# stm32f3driver3.net
KiCad netlist of a schematic drawn in EAGLE
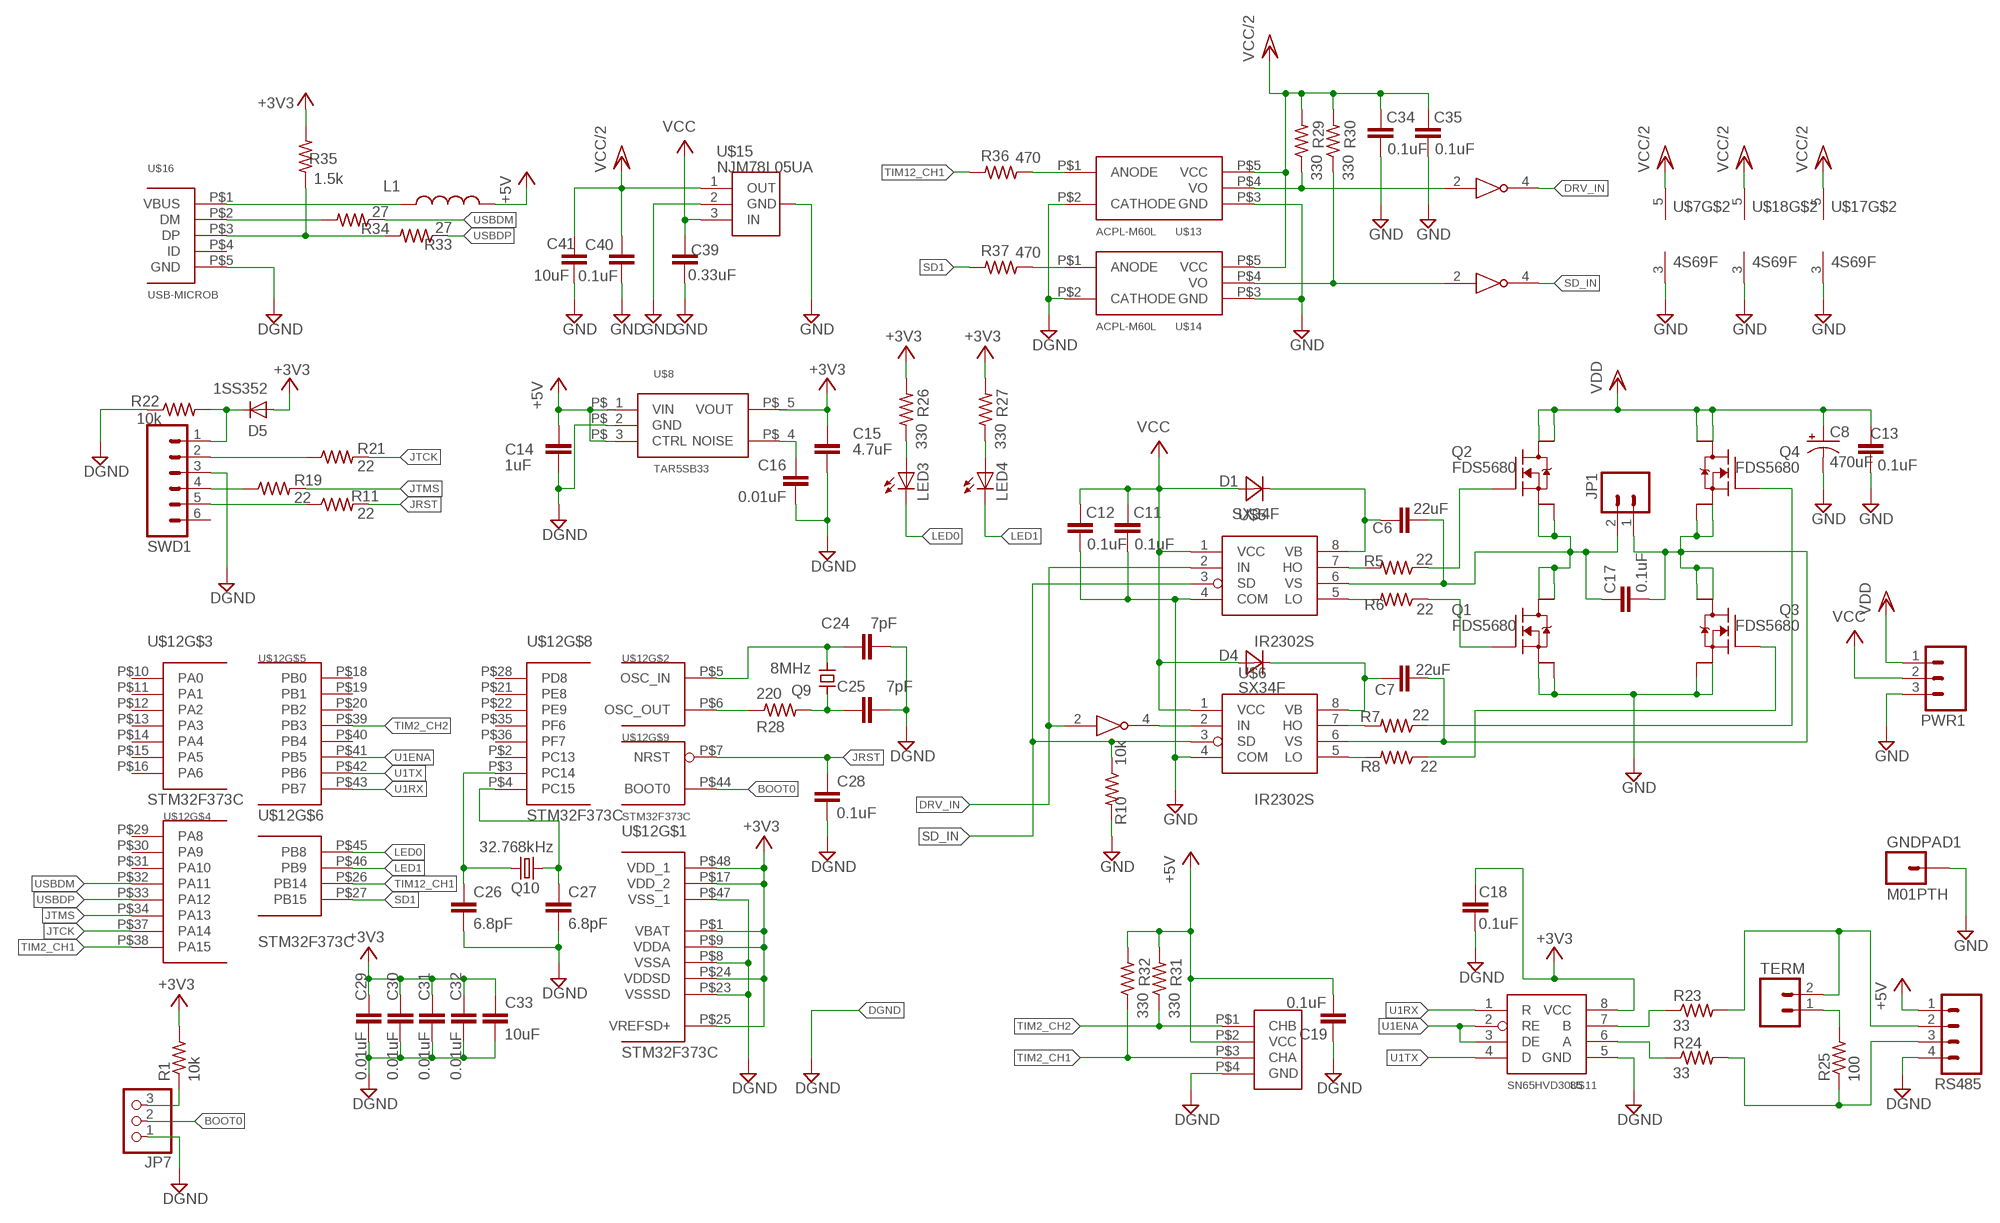
[diagram p0: schematic, sheet 1]

(export (version "E")
  (design (tool "Eeschema 10.0.6"))
  (components
    (comp (ref "C6")
      (value "22uF")
      (footprint "eagle-import:C3225")
      (libsource (lib "eagle-import") (part "C-EUC3225"))
    )
    (comp (ref "C7")
      (value "22uF")
      (footprint "eagle-import:C3225")
      (libsource (lib "eagle-import") (part "C-EUC3225"))
    )
    (comp (ref "C8")
      (value "470uF")
      (footprint "eagle-import:E5-10,5")
      (libsource (lib "eagle-import") (part "CPOL-USE5-10.5"))
    )
    (comp (ref "C11")
      (value "0.1uF")
      (footprint "eagle-import:C0603")
      (libsource (lib "eagle-import") (part "C-EUC0603"))
    )
    (comp (ref "C12")
      (value "0.1uF")
      (footprint "eagle-import:C0603")
      (libsource (lib "eagle-import") (part "C-EUC0603"))
    )
    (comp (ref "C13")
      (value "0.1uF")
      (footprint "eagle-import:C0603")
      (libsource (lib "eagle-import") (part "C-EUC0603"))
    )
    (comp (ref "C14")
      (value "1uF")
      (footprint "eagle-import:C2012")
      (libsource (lib "eagle-import") (part "C-EUC2012"))
    )
    (comp (ref "C15")
      (value "4.7uF")
      (footprint "eagle-import:C2012")
      (libsource (lib "eagle-import") (part "C-EUC2012"))
    )
    (comp (ref "C16")
      (value "0.01uF")
      (footprint "eagle-import:C0603")
      (libsource (lib "eagle-import") (part "C-EUC0603"))
    )
    (comp (ref "C17")
      (value "0.1uF")
      (footprint "eagle-import:C0603")
      (libsource (lib "eagle-import") (part "C-EUC0603"))
    )
    (comp (ref "C18")
      (value "0.1uF")
      (footprint "eagle-import:C1608")
      (libsource (lib "eagle-import") (part "C-EUC1608"))
    )
    (comp (ref "C19")
      (value "0.1uF")
      (footprint "eagle-import:C0603")
      (libsource (lib "eagle-import") (part "C-EUC0603"))
    )
    (comp (ref "C24")
      (value "7pF")
      (footprint "eagle-import:C0603")
      (libsource (lib "eagle-import") (part "C-EUC0603"))
    )
    (comp (ref "C25")
      (value "7pF")
      (footprint "eagle-import:C0603")
      (libsource (lib "eagle-import") (part "C-EUC0603"))
    )
    (comp (ref "C26")
      (value "6.8pF")
      (footprint "eagle-import:C0603")
      (libsource (lib "eagle-import") (part "C-EUC0603"))
    )
    (comp (ref "C27")
      (value "6.8pF")
      (footprint "eagle-import:C0603")
      (libsource (lib "eagle-import") (part "C-EUC0603"))
    )
    (comp (ref "C28")
      (value "0.1uF")
      (footprint "eagle-import:C0603")
      (libsource (lib "eagle-import") (part "C-EUC0603"))
    )
    (comp (ref "C29")
      (value "0.01uF")
      (footprint "eagle-import:C0603")
      (libsource (lib "eagle-import") (part "C-EUC0603"))
    )
    (comp (ref "C30")
      (value "0.01uF")
      (footprint "eagle-import:C0603")
      (libsource (lib "eagle-import") (part "C-EUC0603"))
    )
    (comp (ref "C31")
      (value "0.01uF")
      (footprint "eagle-import:C0603")
      (libsource (lib "eagle-import") (part "C-EUC0603"))
    )
    (comp (ref "C32")
      (value "0.01uF")
      (footprint "eagle-import:C0603")
      (libsource (lib "eagle-import") (part "C-EUC0603"))
    )
    (comp (ref "C33")
      (value "10uF")
      (footprint "eagle-import:C3216")
      (libsource (lib "eagle-import") (part "C-EUC3216"))
    )
    (comp (ref "C34")
      (value "0.1uF")
      (footprint "eagle-import:C0603")
      (libsource (lib "eagle-import") (part "C-EUC0603"))
    )
    (comp (ref "C35")
      (value "0.1uF")
      (footprint "eagle-import:C0603")
      (libsource (lib "eagle-import") (part "C-EUC0603"))
    )
    (comp (ref "C39")
      (value "0.33uF")
      (footprint "eagle-import:C0805")
      (libsource (lib "eagle-import") (part "C-EUC0805"))
    )
    (comp (ref "C40")
      (value "0.1uF")
      (footprint "eagle-import:C0603")
      (libsource (lib "eagle-import") (part "C-EUC0603"))
    )
    (comp (ref "C41")
      (value "10uF")
      (footprint "eagle-import:C3216")
      (libsource (lib "eagle-import") (part "C-EUC3216"))
    )
    (comp (ref "D1")
      (value "SX34F")
      (footprint "eagle-import:SMA")
      (libsource (lib "eagle-import") (part "MBRA340T3"))
    )
    (comp (ref "D4")
      (value "SX34F")
      (footprint "eagle-import:SMA")
      (libsource (lib "eagle-import") (part "MBRA340T3"))
    )
    (comp (ref "D5")
      (value "1SS352")
      (footprint "eagle-import:SOD-323")
      (libsource (lib "eagle-import") (part "DIODESOD"))
    )
    (comp (ref "GNDPAD1")
      (value "M01PTH")
      (footprint "eagle-import:1X01")
      (libsource (lib "eagle-import") (part "M01PTH"))
    )
    (comp (ref "JP1")
      (value "M02PTH3")
      (footprint "eagle-import:1X02_LONGPADS")
      (libsource (lib "eagle-import") (part "M02PTH3"))
    )
    (comp (ref "JP7")
      (value "PINHD-1X3")
      (footprint "eagle-import:1X03")
      (libsource (lib "eagle-import") (part "PINHD-1X3"))
    )
    (comp (ref "L1")
      (value "L-USL3216C")
      (footprint "eagle-import:L3216C")
      (libsource (lib "eagle-import") (part "L-USL3216C"))
    )
    (comp (ref "LED3")
      (value "LED0603")
      (footprint "eagle-import:LED-0603")
      (libsource (lib "eagle-import") (part "LED0603"))
    )
    (comp (ref "LED4")
      (value "LED0603")
      (footprint "eagle-import:LED-0603")
      (libsource (lib "eagle-import") (part "LED0603"))
    )
    (comp (ref "PWR1")
      (value "M03LONGPADS")
      (footprint "eagle-import:1X03_LONGPADS")
      (libsource (lib "eagle-import") (part "M03LONGPADS"))
    )
    (comp (ref "Q1")
      (value "FDS5680")
      (footprint "eagle-import:1206-8CHIP-FET")
      (libsource (lib "eagle-import") (part "FDS5680"))
    )
    (comp (ref "Q2")
      (value "FDS5680")
      (footprint "eagle-import:1206-8CHIP-FET")
      (libsource (lib "eagle-import") (part "FDS5680"))
    )
    (comp (ref "Q3")
      (value "FDS5680")
      (footprint "eagle-import:1206-8CHIP-FET")
      (libsource (lib "eagle-import") (part "FDS5680"))
    )
    (comp (ref "Q4")
      (value "FDS5680")
      (footprint "eagle-import:1206-8CHIP-FET")
      (libsource (lib "eagle-import") (part "FDS5680"))
    )
    (comp (ref "Q9")
      (value "8MHz")
      (footprint "eagle-import:SMD5032")
      (libsource (lib "eagle-import") (part "NX5032GA"))
    )
    (comp (ref "Q10")
      (value "32.768kHz")
      (footprint "eagle-import:TC26H")
      (libsource (lib "eagle-import") (part "CRYSTALTC26H"))
    )
    (comp (ref "R1")
      (value "10k")
      (footprint "eagle-import:R0603")
      (libsource (lib "eagle-import") (part "R-US_R0603"))
    )
    (comp (ref "R5")
      (value "22")
      (footprint "eagle-import:R0603")
      (libsource (lib "eagle-import") (part "R-US_R0603"))
    )
    (comp (ref "R6")
      (value "22")
      (footprint "eagle-import:R0603")
      (libsource (lib "eagle-import") (part "R-US_R0603"))
    )
    (comp (ref "R7")
      (value "22")
      (footprint "eagle-import:R0603")
      (libsource (lib "eagle-import") (part "R-US_R0603"))
    )
    (comp (ref "R8")
      (value "22")
      (footprint "eagle-import:R0603")
      (libsource (lib "eagle-import") (part "R-US_R0603"))
    )
    (comp (ref "R10")
      (value "10k")
      (footprint "eagle-import:R0603")
      (libsource (lib "eagle-import") (part "R-US_R0603"))
    )
    (comp (ref "R11")
      (value "22")
      (footprint "eagle-import:R0603")
      (libsource (lib "eagle-import") (part "R-US_R0603"))
    )
    (comp (ref "R19")
      (value "22")
      (footprint "eagle-import:R0603")
      (libsource (lib "eagle-import") (part "R-US_R0603"))
    )
    (comp (ref "R21")
      (value "22")
      (footprint "eagle-import:R0603")
      (libsource (lib "eagle-import") (part "R-US_R0603"))
    )
    (comp (ref "R22")
      (value "10k")
      (footprint "eagle-import:R0603")
      (libsource (lib "eagle-import") (part "R-US_R0603"))
    )
    (comp (ref "R23")
      (value "33")
      (footprint "eagle-import:R0603")
      (libsource (lib "eagle-import") (part "R-US_R0603"))
    )
    (comp (ref "R24")
      (value "33")
      (footprint "eagle-import:R0603")
      (libsource (lib "eagle-import") (part "R-US_R0603"))
    )
    (comp (ref "R25")
      (value "100")
      (footprint "eagle-import:R0603")
      (libsource (lib "eagle-import") (part "R-US_R0603"))
    )
    (comp (ref "R26")
      (value "330")
      (footprint "eagle-import:R0603")
      (libsource (lib "eagle-import") (part "R-US_R0603"))
    )
    (comp (ref "R27")
      (value "330")
      (footprint "eagle-import:R0603")
      (libsource (lib "eagle-import") (part "R-US_R0603"))
    )
    (comp (ref "R28")
      (value "220")
      (footprint "eagle-import:R0603")
      (libsource (lib "eagle-import") (part "R-US_R0603"))
    )
    (comp (ref "R29")
      (value "330")
      (footprint "eagle-import:R0603")
      (libsource (lib "eagle-import") (part "R-US_R0603"))
    )
    (comp (ref "R30")
      (value "330")
      (footprint "eagle-import:R0603")
      (libsource (lib "eagle-import") (part "R-US_R0603"))
    )
    (comp (ref "R31")
      (value "330")
      (footprint "eagle-import:R0603")
      (libsource (lib "eagle-import") (part "R-US_R0603"))
    )
    (comp (ref "R32")
      (value "330")
      (footprint "eagle-import:R0603")
      (libsource (lib "eagle-import") (part "R-US_R0603"))
    )
    (comp (ref "R33")
      (value "27")
      (footprint "eagle-import:R0603")
      (libsource (lib "eagle-import") (part "R-US_R0603"))
    )
    (comp (ref "R34")
      (value "27")
      (footprint "eagle-import:R0603")
      (libsource (lib "eagle-import") (part "R-US_R0603"))
    )
    (comp (ref "R35")
      (value "1.5k")
      (footprint "eagle-import:R0603")
      (libsource (lib "eagle-import") (part "R-US_R0603"))
    )
    (comp (ref "R36")
      (value "470")
      (footprint "eagle-import:R0603")
      (libsource (lib "eagle-import") (part "R-US_R0603"))
    )
    (comp (ref "R37")
      (value "470")
      (footprint "eagle-import:R0603")
      (libsource (lib "eagle-import") (part "R-US_R0603"))
    )
    (comp (ref "RS485")
      (value "M04PTH")
      (footprint "eagle-import:1X04")
      (libsource (lib "eagle-import") (part "M04PTH"))
    )
    (comp (ref "SWD1")
      (value "M06SIP")
      (footprint "eagle-import:1X06")
      (libsource (lib "eagle-import") (part "M06SIP"))
    )
    (comp (ref "TERM")
      (value "M02PTH")
      (footprint "eagle-import:1X02")
      (libsource (lib "eagle-import") (part "M02PTH"))
    )
    (comp (ref "U$5")
      (value "IR2302S")
      (footprint "eagle-import:SO8")
      (libsource (lib "eagle-import") (part "IR2302S"))
    )
    (comp (ref "U$6")
      (value "IR2302S")
      (footprint "eagle-import:SO8")
      (libsource (lib "eagle-import") (part "IR2302S"))
    )
    (comp (ref "U$7")
      (value "4S69F")
      (footprint "eagle-import:SOT23-5")
      (libsource (lib "eagle-import") (part "4S69F"))
    )
    (comp (ref "U$8")
      (value "TAR5SB33")
      (footprint "eagle-import:TAR5SB33")
      (libsource (lib "eagle-import") (part "TAR5SB33"))
    )
    (comp (ref "U$10")
      (value "HEDS9701-C54")
      (footprint "eagle-import:HEDS9701")
      (libsource (lib "eagle-import") (part "HEDS9701-C54"))
    )
    (comp (ref "U$11")
      (value "SN65HVD3085")
      (footprint "eagle-import:SO8")
      (libsource (lib "eagle-import") (part "SN65HVD3085"))
    )
    (comp (ref "U$12")
      (value "STM32F373C")
      (footprint "eagle-import:TQFP48")
      (libsource (lib "eagle-import") (part "STM32F373C"))
    )
    (comp (ref "U$13")
      (value "ACPL-M60L")
      (footprint "eagle-import:SO5")
      (libsource (lib "eagle-import") (part "ACPL-M60L"))
    )
    (comp (ref "U$14")
      (value "ACPL-M60L")
      (footprint "eagle-import:SO5")
      (libsource (lib "eagle-import") (part "ACPL-M60L"))
    )
    (comp (ref "U$15")
      (value "NJM78L05UA")
      (footprint "eagle-import:SOT89")
      (libsource (lib "eagle-import") (part "NJM78L05UA"))
    )
    (comp (ref "U$16")
      (value "USB-MICROB")
      (footprint "eagle-import:USB_MICROB")
      (libsource (lib "eagle-import") (part "USB-MICROB"))
    )
    (comp (ref "U$17")
      (value "4S69F")
      (footprint "eagle-import:SOT23-5")
      (libsource (lib "eagle-import") (part "4S69F"))
    )
    (comp (ref "U$18")
      (value "4S69F")
      (footprint "eagle-import:SOT23-5")
      (libsource (lib "eagle-import") (part "4S69F"))
    )
  )
  (nets
    (net (code "1") (name "+3V3") (class "Default")
      (node (ref "C15") (pin "1") (pinfunction "1_1") (pintype "passive"))
      (node (ref "C18") (pin "1") (pinfunction "1_1") (pintype "passive"))
      (node (ref "C29") (pin "1") (pinfunction "1_1") (pintype "passive"))
      (node (ref "C30") (pin "1") (pinfunction "1_1") (pintype "passive"))
      (node (ref "C31") (pin "1") (pinfunction "1_1") (pintype "passive"))
      (node (ref "C32") (pin "1") (pinfunction "1_1") (pintype "passive"))
      (node (ref "C33") (pin "1") (pinfunction "1_1") (pintype "passive"))
      (node (ref "D5") (pin "2") (pinfunction "A_2") (pintype "passive"))
      (node (ref "R1") (pin "2") (pinfunction "2_2") (pintype "passive"))
      (node (ref "R26") (pin "2") (pinfunction "2_2") (pintype "passive"))
      (node (ref "R27") (pin "2") (pinfunction "2_2") (pintype "passive"))
      (node (ref "R35") (pin "2") (pinfunction "2_2") (pintype "passive"))
      (node (ref "U$11") (pin "8") (pinfunction "VCC_8") (pintype "power_in"))
      (node (ref "U$12") (pin "P$1") (pinfunction "VBAT_P$1") (pintype "power_in"))
      (node (ref "U$12") (pin "P$17") (pinfunction "VDD_2_P$17") (pintype "power_in"))
      (node (ref "U$12") (pin "P$24") (pinfunction "VDDSD_P$24") (pintype "power_in"))
      (node (ref "U$12") (pin "P$25") (pinfunction "VREFSD+_P$25") (pintype "input"))
      (node (ref "U$12") (pin "P$48") (pinfunction "VDD_1_P$48") (pintype "power_in"))
      (node (ref "U$12") (pin "P$9") (pinfunction "VDDA_P$9") (pintype "power_in"))
      (node (ref "U$8") (pin "P$_5") (pinfunction "VOUT_P$_5") (pintype "power_in"))
    )
    (net (code "2") (name "+5V") (class "Default")
      (node (ref "C14") (pin "1") (pinfunction "1_1") (pintype "passive"))
      (node (ref "C19") (pin "2") (pinfunction "2_2") (pintype "passive"))
      (node (ref "L1") (pin "2") (pinfunction "2_2") (pintype "passive"))
      (node (ref "R31") (pin "2") (pinfunction "2_2") (pintype "passive"))
      (node (ref "R32") (pin "2") (pinfunction "2_2") (pintype "passive"))
      (node (ref "RS485") (pin "1") (pinfunction "1_1") (pintype "passive"))
      (node (ref "U$10") (pin "P$2") (pinfunction "VCC_P$2") (pintype "power_in"))
      (node (ref "U$8") (pin "P$_1") (pinfunction "VIN_P$_1") (pintype "power_in"))
      (node (ref "U$8") (pin "P$_3") (pinfunction "CTRL_P$_3") (pintype "input"))
    )
    (net (code "3") (name "BOOT0") (class "Default")
      (node (ref "JP7") (pin "2") (pinfunction "2_2") (pintype "passive"))
      (node (ref "U$12") (pin "P$44") (pinfunction "BOOT0_P$44") (pintype "input"))
    )
    (net (code "4") (name "DGND") (class "Default")
      (node (ref "C14") (pin "2") (pinfunction "2_2") (pintype "passive"))
      (node (ref "C15") (pin "2") (pinfunction "2_2") (pintype "passive"))
      (node (ref "C16") (pin "2") (pinfunction "2_2") (pintype "passive"))
      (node (ref "C18") (pin "2") (pinfunction "2_2") (pintype "passive"))
      (node (ref "C19") (pin "1") (pinfunction "1_1") (pintype "passive"))
      (node (ref "C24") (pin "2") (pinfunction "2_2") (pintype "passive"))
      (node (ref "C25") (pin "2") (pinfunction "2_2") (pintype "passive"))
      (node (ref "C26") (pin "2") (pinfunction "2_2") (pintype "passive"))
      (node (ref "C27") (pin "2") (pinfunction "2_2") (pintype "passive"))
      (node (ref "C28") (pin "2") (pinfunction "2_2") (pintype "passive"))
      (node (ref "C29") (pin "2") (pinfunction "2_2") (pintype "passive"))
      (node (ref "C30") (pin "2") (pinfunction "2_2") (pintype "passive"))
      (node (ref "C31") (pin "2") (pinfunction "2_2") (pintype "passive"))
      (node (ref "C32") (pin "2") (pinfunction "2_2") (pintype "passive"))
      (node (ref "C33") (pin "2") (pinfunction "2_2") (pintype "passive"))
      (node (ref "JP7") (pin "1") (pinfunction "1_1") (pintype "passive"))
      (node (ref "R22") (pin "1") (pinfunction "1_1") (pintype "passive"))
      (node (ref "RS485") (pin "4") (pinfunction "4_4") (pintype "passive"))
      (node (ref "SWD1") (pin "3") (pinfunction "3_3") (pintype "passive"))
      (node (ref "U$10") (pin "P$4") (pinfunction "GND_P$4") (pintype "power_in"))
      (node (ref "U$11") (pin "5") (pinfunction "GND_5") (pintype "power_in"))
      (node (ref "U$12") (pin "P$23") (pinfunction "VSSSD_P$23") (pintype "power_in"))
      (node (ref "U$12") (pin "P$47") (pinfunction "VSS_1_P$47") (pintype "power_in"))
      (node (ref "U$12") (pin "P$8") (pinfunction "VSSA_P$8") (pintype "power_in"))
      (node (ref "U$13") (pin "P$2") (pinfunction "CATHODE_P$2") (pintype "power_in"))
      (node (ref "U$14") (pin "P$2") (pinfunction "CATHODE_P$2") (pintype "power_in"))
      (node (ref "U$16") (pin "P$5") (pinfunction "GND_P$5") (pintype "power_in"))
      (node (ref "U$8") (pin "P$_2") (pinfunction "GND_P$_2") (pintype "power_in"))
    )
    (net (code "5") (name "DRV_IN") (class "Default")
      (node (ref "U$17") (pin "4") (pinfunction "P$2_4") (pintype "bidirectional"))
      (node (ref "U$5") (pin "2") (pinfunction "IN_2") (pintype "input"))
      (node (ref "U$7") (pin "2") (pinfunction "P$1_2") (pintype "bidirectional"))
    )
    (net (code "6") (name "GND") (class "Default")
      (node (ref "C11") (pin "2") (pinfunction "2_2") (pintype "passive"))
      (node (ref "C12") (pin "2") (pinfunction "2_2") (pintype "passive"))
      (node (ref "C13") (pin "2") (pinfunction "2_2") (pintype "passive"))
      (node (ref "C34") (pin "2") (pinfunction "2_2") (pintype "passive"))
      (node (ref "C35") (pin "2") (pinfunction "2_2") (pintype "passive"))
      (node (ref "C39") (pin "2") (pinfunction "2_2") (pintype "passive"))
      (node (ref "C40") (pin "2") (pinfunction "2_2") (pintype "passive"))
      (node (ref "C41") (pin "2") (pinfunction "2_2") (pintype "passive"))
      (node (ref "C8") (pin "-") (pinfunction "-_-") (pintype "passive"))
      (node (ref "GNDPAD1") (pin "1") (pinfunction "1_1") (pintype "passive"))
      (node (ref "PWR1") (pin "3") (pinfunction "3_3") (pintype "passive"))
      (node (ref "Q1") (pin "1") (pinfunction "S_1") (pintype "passive"))
      (node (ref "Q1") (pin "2") (pinfunction "S1_2") (pintype "passive"))
      (node (ref "Q1") (pin "3") (pinfunction "S2_3") (pintype "passive"))
      (node (ref "Q3") (pin "1") (pinfunction "S_1") (pintype "passive"))
      (node (ref "Q3") (pin "2") (pinfunction "S1_2") (pintype "passive"))
      (node (ref "Q3") (pin "3") (pinfunction "S2_3") (pintype "passive"))
      (node (ref "R10") (pin "2") (pinfunction "2_2") (pintype "passive"))
      (node (ref "U$13") (pin "P$3") (pinfunction "GND_P$3") (pintype "power_in"))
      (node (ref "U$14") (pin "P$3") (pinfunction "GND_P$3") (pintype "power_in"))
      (node (ref "U$15") (pin "2") (pinfunction "GND_2") (pintype "bidirectional"))
      (node (ref "U$15") (pin "2@1") (pinfunction "GND2_2@1") (pintype "power_in"))
      (node (ref "U$17") (pin "3") (pinfunction "V-_3") (pintype "power_in"))
      (node (ref "U$18") (pin "3") (pinfunction "V-_3") (pintype "power_in"))
      (node (ref "U$5") (pin "4") (pinfunction "COM_4") (pintype "power_in"))
      (node (ref "U$6") (pin "4") (pinfunction "COM_4") (pintype "power_in"))
      (node (ref "U$7") (pin "3") (pinfunction "V-_3") (pintype "power_in"))
    )
    (net (code "7") (name "JRST") (class "Default")
      (node (ref "C28") (pin "1") (pinfunction "1_1") (pintype "passive"))
      (node (ref "R11") (pin "2") (pinfunction "2_2") (pintype "passive"))
      (node (ref "U$12") (pin "P$7") (pinfunction "NRST_P$7") (pintype "input"))
    )
    (net (code "8") (name "JTCK") (class "Default")
      (node (ref "R21") (pin "2") (pinfunction "2_2") (pintype "passive"))
      (node (ref "U$12") (pin "P$37") (pinfunction "PA14_P$37") (pintype "bidirectional"))
    )
    (net (code "9") (name "JTMS") (class "Default")
      (node (ref "R19") (pin "2") (pinfunction "2_2") (pintype "passive"))
      (node (ref "U$12") (pin "P$34") (pinfunction "PA13_P$34") (pintype "bidirectional"))
    )
    (net (code "10") (name "LED0") (class "Default")
      (node (ref "LED3") (pin "C") (pinfunction "C_C") (pintype "passive"))
      (node (ref "U$12") (pin "P$45") (pinfunction "PB8_P$45") (pintype "bidirectional"))
    )
    (net (code "11") (name "LED1") (class "Default")
      (node (ref "LED4") (pin "C") (pinfunction "C_C") (pintype "passive"))
      (node (ref "U$12") (pin "P$46") (pinfunction "PB9_P$46") (pintype "bidirectional"))
    )
    (net (code "12") (name "Net-(D5-C)") (class "Default")
      (node (ref "D5") (pin "1") (pinfunction "C_1") (pintype "passive"))
      (node (ref "R22") (pin "2") (pinfunction "2_2") (pintype "passive"))
      (node (ref "SWD1") (pin "1") (pinfunction "1_1") (pintype "passive"))
    )
    (net (code "13") (name "Net-(JP7-Pad3)") (class "Default")
      (node (ref "JP7") (pin "3") (pinfunction "3_3") (pintype "passive"))
      (node (ref "R1") (pin "1") (pinfunction "1_1") (pintype "passive"))
    )
    (net (code "14") (name "Net-(LED3-PadA)") (class "Default")
      (node (ref "LED3") (pin "A") (pinfunction "A_A") (pintype "passive"))
      (node (ref "R26") (pin "1") (pinfunction "1_1") (pintype "passive"))
    )
    (net (code "15") (name "Net-(LED4-PadA)") (class "Default")
      (node (ref "LED4") (pin "A") (pinfunction "A_A") (pintype "passive"))
      (node (ref "R27") (pin "1") (pinfunction "1_1") (pintype "passive"))
    )
    (net (code "16") (name "Net-(Q1-D)") (class "Default")
      (node (ref "C17") (pin "1") (pinfunction "1_1") (pintype "passive"))
      (node (ref "C6") (pin "2") (pinfunction "2_2") (pintype "passive"))
      (node (ref "JP1") (pin "2") (pinfunction "2_2") (pintype "passive"))
      (node (ref "Q1") (pin "5") (pinfunction "D_5") (pintype "passive"))
      (node (ref "Q1") (pin "6") (pinfunction "D1_6") (pintype "passive"))
      (node (ref "Q1") (pin "7") (pinfunction "D2_7") (pintype "passive"))
      (node (ref "Q1") (pin "8") (pinfunction "D3_8") (pintype "passive"))
      (node (ref "Q2") (pin "1") (pinfunction "S_1") (pintype "passive"))
      (node (ref "Q2") (pin "2") (pinfunction "S1_2") (pintype "passive"))
      (node (ref "Q2") (pin "3") (pinfunction "S2_3") (pintype "passive"))
      (node (ref "U$5") (pin "6") (pinfunction "VS_6") (pintype "bidirectional"))
    )
    (net (code "17") (name "Net-(Q1-G)") (class "Default")
      (node (ref "Q1") (pin "4") (pinfunction "G_4") (pintype "passive"))
      (node (ref "R6") (pin "1") (pinfunction "1_1") (pintype "passive"))
    )
    (net (code "18") (name "Net-(Q2-G)") (class "Default")
      (node (ref "Q2") (pin "4") (pinfunction "G_4") (pintype "passive"))
      (node (ref "R5") (pin "1") (pinfunction "1_1") (pintype "passive"))
    )
    (net (code "19") (name "Net-(Q3-D)") (class "Default")
      (node (ref "C17") (pin "2") (pinfunction "2_2") (pintype "passive"))
      (node (ref "C7") (pin "2") (pinfunction "2_2") (pintype "passive"))
      (node (ref "JP1") (pin "1") (pinfunction "1_1") (pintype "passive"))
      (node (ref "Q3") (pin "5") (pinfunction "D_5") (pintype "passive"))
      (node (ref "Q3") (pin "6") (pinfunction "D1_6") (pintype "passive"))
      (node (ref "Q3") (pin "7") (pinfunction "D2_7") (pintype "passive"))
      (node (ref "Q3") (pin "8") (pinfunction "D3_8") (pintype "passive"))
      (node (ref "Q4") (pin "1") (pinfunction "S_1") (pintype "passive"))
      (node (ref "Q4") (pin "2") (pinfunction "S1_2") (pintype "passive"))
      (node (ref "Q4") (pin "3") (pinfunction "S2_3") (pintype "passive"))
      (node (ref "U$6") (pin "6") (pinfunction "VS_6") (pintype "bidirectional"))
    )
    (net (code "20") (name "Net-(Q3-G)") (class "Default")
      (node (ref "Q3") (pin "4") (pinfunction "G_4") (pintype "passive"))
      (node (ref "R8") (pin "1") (pinfunction "1_1") (pintype "passive"))
    )
    (net (code "21") (name "Net-(Q4-G)") (class "Default")
      (node (ref "Q4") (pin "4") (pinfunction "G_4") (pintype "passive"))
      (node (ref "R7") (pin "1") (pinfunction "1_1") (pintype "passive"))
    )
    (net (code "22") (name "Net-(Q9-P$1)") (class "Default")
      (node (ref "C25") (pin "1") (pinfunction "1_1") (pintype "passive"))
      (node (ref "Q9") (pin "P1") (pinfunction "P$1_P1") (pintype "bidirectional"))
      (node (ref "R28") (pin "2") (pinfunction "2_2") (pintype "passive"))
    )
    (net (code "23") (name "Net-(Q9-P$2)") (class "Default")
      (node (ref "C24") (pin "1") (pinfunction "1_1") (pintype "passive"))
      (node (ref "Q9") (pin "P2") (pinfunction "P$2_P2") (pintype "bidirectional"))
      (node (ref "U$12") (pin "P$5") (pinfunction "OSC_IN_P$5") (pintype "input"))
    )
    (net (code "24") (name "Net-(R11-Pad1)") (class "Default")
      (node (ref "R11") (pin "1") (pinfunction "1_1") (pintype "passive"))
      (node (ref "SWD1") (pin "5") (pinfunction "5_5") (pintype "passive"))
    )
    (net (code "25") (name "Net-(R19-Pad1)") (class "Default")
      (node (ref "R19") (pin "1") (pinfunction "1_1") (pintype "passive"))
      (node (ref "SWD1") (pin "4") (pinfunction "4_4") (pintype "passive"))
    )
    (net (code "26") (name "Net-(R21-Pad1)") (class "Default")
      (node (ref "R21") (pin "1") (pinfunction "1_1") (pintype "passive"))
      (node (ref "SWD1") (pin "2") (pinfunction "2_2") (pintype "passive"))
    )
    (net (code "27") (name "Net-(R23-Pad2)") (class "Default")
      (node (ref "R23") (pin "2") (pinfunction "2_2") (pintype "passive"))
      (node (ref "RS485") (pin "2") (pinfunction "2_2") (pintype "passive"))
      (node (ref "TERM") (pin "2") (pinfunction "2_2") (pintype "passive"))
    )
    (net (code "28") (name "Net-(R24-Pad2)") (class "Default")
      (node (ref "R24") (pin "2") (pinfunction "2_2") (pintype "passive"))
      (node (ref "R25") (pin "1") (pinfunction "1_1") (pintype "passive"))
      (node (ref "RS485") (pin "3") (pinfunction "3_3") (pintype "passive"))
    )
    (net (code "29") (name "Net-(R25-Pad2)") (class "Default")
      (node (ref "R25") (pin "2") (pinfunction "2_2") (pintype "passive"))
      (node (ref "TERM") (pin "1") (pinfunction "1_1") (pintype "passive"))
    )
    (net (code "30") (name "Net-(U$5-HO)") (class "Default")
      (node (ref "R5") (pin "2") (pinfunction "2_2") (pintype "passive"))
      (node (ref "U$5") (pin "7") (pinfunction "HO_7") (pintype "output"))
    )
    (net (code "31") (name "Net-(U$5-LO)") (class "Default")
      (node (ref "R6") (pin "2") (pinfunction "2_2") (pintype "passive"))
      (node (ref "U$5") (pin "5") (pinfunction "LO_5") (pintype "output"))
    )
    (net (code "32") (name "Net-(U$5-VB)") (class "Default")
      (node (ref "C6") (pin "1") (pinfunction "1_1") (pintype "passive"))
      (node (ref "D1") (pin "C") (pinfunction "C_C") (pintype "passive"))
      (node (ref "U$5") (pin "8") (pinfunction "VB_8") (pintype "bidirectional"))
    )
    (net (code "33") (name "Net-(U$6-HO)") (class "Default")
      (node (ref "R7") (pin "2") (pinfunction "2_2") (pintype "passive"))
      (node (ref "U$6") (pin "7") (pinfunction "HO_7") (pintype "output"))
    )
    (net (code "34") (name "Net-(U$6-IN)") (class "Default")
      (node (ref "U$6") (pin "2") (pinfunction "IN_2") (pintype "input"))
      (node (ref "U$7") (pin "4") (pinfunction "P$2_4") (pintype "bidirectional"))
    )
    (net (code "35") (name "Net-(U$6-LO)") (class "Default")
      (node (ref "R8") (pin "2") (pinfunction "2_2") (pintype "passive"))
      (node (ref "U$6") (pin "5") (pinfunction "LO_5") (pintype "output"))
    )
    (net (code "36") (name "Net-(U$6-VB)") (class "Default")
      (node (ref "C7") (pin "1") (pinfunction "1_1") (pintype "passive"))
      (node (ref "D4") (pin "C") (pinfunction "C_C") (pintype "passive"))
      (node (ref "U$6") (pin "8") (pinfunction "VB_8") (pintype "bidirectional"))
    )
    (net (code "37") (name "Net-(U$8-NOISE)") (class "Default")
      (node (ref "C16") (pin "1") (pinfunction "1_1") (pintype "passive"))
      (node (ref "U$8") (pin "P$_4") (pinfunction "NOISE_P$_4") (pintype "input"))
    )
    (net (code "38") (name "Net-(U$11-A)") (class "Default")
      (node (ref "R24") (pin "1") (pinfunction "1_1") (pintype "passive"))
      (node (ref "U$11") (pin "6") (pinfunction "A_6") (pintype "bidirectional"))
    )
    (net (code "39") (name "Net-(U$11-B)") (class "Default")
      (node (ref "R23") (pin "1") (pinfunction "1_1") (pintype "passive"))
      (node (ref "U$11") (pin "7") (pinfunction "B_7") (pintype "bidirectional"))
    )
    (net (code "40") (name "Net-(U$12B-OSC_OUT)") (class "Default")
      (node (ref "R28") (pin "1") (pinfunction "1_1") (pintype "passive"))
      (node (ref "U$12") (pin "P$6") (pinfunction "OSC_OUT_P$6") (pintype "output"))
    )
    (net (code "41") (name "Net-(U$12G-PC14)") (class "Default")
      (node (ref "C26") (pin "1") (pinfunction "1_1") (pintype "passive"))
      (node (ref "Q10") (pin "1") (pinfunction "1_1") (pintype "passive"))
      (node (ref "U$12") (pin "P$3") (pinfunction "PC14_P$3") (pintype "bidirectional"))
    )
    (net (code "42") (name "Net-(U$12G-PC15)") (class "Default")
      (node (ref "C27") (pin "1") (pinfunction "1_1") (pintype "passive"))
      (node (ref "Q10") (pin "2") (pinfunction "2_2") (pintype "passive"))
      (node (ref "U$12") (pin "P$4") (pinfunction "PC15_P$4") (pintype "bidirectional"))
    )
    (net (code "43") (name "Net-(U$13-ANODE)") (class "Default")
      (node (ref "R36") (pin "1") (pinfunction "1_1") (pintype "passive"))
      (node (ref "U$13") (pin "P$1") (pinfunction "ANODE_P$1") (pintype "power_in"))
    )
    (net (code "44") (name "Net-(U$13-VO)") (class "Default")
      (node (ref "R29") (pin "1") (pinfunction "1_1") (pintype "passive"))
      (node (ref "U$13") (pin "P$4") (pinfunction "VO_P$4") (pintype "output"))
      (node (ref "U$17") (pin "2") (pinfunction "P$1_2") (pintype "bidirectional"))
    )
    (net (code "45") (name "Net-(U$14-ANODE)") (class "Default")
      (node (ref "R37") (pin "1") (pinfunction "1_1") (pintype "passive"))
      (node (ref "U$14") (pin "P$1") (pinfunction "ANODE_P$1") (pintype "power_in"))
    )
    (net (code "46") (name "Net-(U$14-VO)") (class "Default")
      (node (ref "R30") (pin "1") (pinfunction "1_1") (pintype "passive"))
      (node (ref "U$14") (pin "P$4") (pinfunction "VO_P$4") (pintype "output"))
      (node (ref "U$18") (pin "2") (pinfunction "P$1_2") (pintype "bidirectional"))
    )
    (net (code "47") (name "Net-(U$16-DM)") (class "Default")
      (node (ref "R34") (pin "2") (pinfunction "2_2") (pintype "passive"))
      (node (ref "U$16") (pin "P$2") (pinfunction "DM_P$2") (pintype "bidirectional"))
    )
    (net (code "48") (name "Net-(U$16-DP)") (class "Default")
      (node (ref "R33") (pin "2") (pinfunction "2_2") (pintype "passive"))
      (node (ref "R35") (pin "1") (pinfunction "1_1") (pintype "passive"))
      (node (ref "U$16") (pin "P$3") (pinfunction "DP_P$3") (pintype "bidirectional"))
    )
    (net (code "49") (name "Net-(U$16-VBUS)") (class "Default")
      (node (ref "L1") (pin "1") (pinfunction "1_1") (pintype "passive"))
      (node (ref "U$16") (pin "P$1") (pinfunction "VBUS_P$1") (pintype "power_in"))
    )
    (net (code "50") (name "SD1") (class "Default")
      (node (ref "R37") (pin "2") (pinfunction "2_2") (pintype "passive"))
      (node (ref "U$12") (pin "P$27") (pinfunction "PB15_P$27") (pintype "bidirectional"))
    )
    (net (code "51") (name "SD_IN") (class "Default")
      (node (ref "R10") (pin "1") (pinfunction "1_1") (pintype "passive"))
      (node (ref "U$18") (pin "4") (pinfunction "P$2_4") (pintype "bidirectional"))
      (node (ref "U$5") (pin "3") (pinfunction "SD_3") (pintype "input"))
      (node (ref "U$6") (pin "3") (pinfunction "SD_3") (pintype "input"))
    )
    (net (code "52") (name "TIM2_CH1") (class "Default")
      (node (ref "R32") (pin "1") (pinfunction "1_1") (pintype "passive"))
      (node (ref "U$10") (pin "P$3") (pinfunction "CHA_P$3") (pintype "output"))
      (node (ref "U$12") (pin "P$38") (pinfunction "PA15_P$38") (pintype "bidirectional"))
    )
    (net (code "53") (name "TIM2_CH2") (class "Default")
      (node (ref "R31") (pin "1") (pinfunction "1_1") (pintype "passive"))
      (node (ref "U$10") (pin "P$1") (pinfunction "CHB_P$1") (pintype "output"))
      (node (ref "U$12") (pin "P$39") (pinfunction "PB3_P$39") (pintype "bidirectional"))
    )
    (net (code "54") (name "TIM12_CH1") (class "Default")
      (node (ref "R36") (pin "2") (pinfunction "2_2") (pintype "passive"))
      (node (ref "U$12") (pin "P$26") (pinfunction "PB14_P$26") (pintype "bidirectional"))
    )
    (net (code "55") (name "U1ENA") (class "Default")
      (node (ref "U$11") (pin "2") (pinfunction "RE_2") (pintype "input"))
      (node (ref "U$11") (pin "3") (pinfunction "DE_3") (pintype "input"))
      (node (ref "U$12") (pin "P$41") (pinfunction "PB5_P$41") (pintype "bidirectional"))
    )
    (net (code "56") (name "U1RX") (class "Default")
      (node (ref "U$11") (pin "1") (pinfunction "R_1") (pintype "output"))
      (node (ref "U$12") (pin "P$43") (pinfunction "PB7_P$43") (pintype "bidirectional"))
    )
    (net (code "57") (name "U1TX") (class "Default")
      (node (ref "U$11") (pin "4") (pinfunction "D_4") (pintype "input"))
      (node (ref "U$12") (pin "P$42") (pinfunction "PB6_P$42") (pintype "bidirectional"))
    )
    (net (code "58") (name "USBDM") (class "Default")
      (node (ref "R34") (pin "1") (pinfunction "1_1") (pintype "passive"))
      (node (ref "U$12") (pin "P$32") (pinfunction "PA11_P$32") (pintype "bidirectional"))
    )
    (net (code "59") (name "USBDP") (class "Default")
      (node (ref "R33") (pin "1") (pinfunction "1_1") (pintype "passive"))
      (node (ref "U$12") (pin "P$33") (pinfunction "PA12_P$33") (pintype "bidirectional"))
    )
    (net (code "60") (name "VCC") (class "Default")
      (node (ref "C11") (pin "1") (pinfunction "1_1") (pintype "passive"))
      (node (ref "C12") (pin "1") (pinfunction "1_1") (pintype "passive"))
      (node (ref "C39") (pin "1") (pinfunction "1_1") (pintype "passive"))
      (node (ref "D1") (pin "A") (pinfunction "A_A") (pintype "passive"))
      (node (ref "D4") (pin "A") (pinfunction "A_A") (pintype "passive"))
      (node (ref "PWR1") (pin "2") (pinfunction "2_2") (pintype "passive"))
      (node (ref "U$15") (pin "3") (pinfunction "IN_3") (pintype "bidirectional"))
      (node (ref "U$5") (pin "1") (pinfunction "VCC_1") (pintype "power_in"))
      (node (ref "U$6") (pin "1") (pinfunction "VCC_1") (pintype "power_in"))
    )
    (net (code "61") (name "VCC{slash}2") (class "Default")
      (node (ref "C34") (pin "1") (pinfunction "1_1") (pintype "passive"))
      (node (ref "C35") (pin "1") (pinfunction "1_1") (pintype "passive"))
      (node (ref "C40") (pin "1") (pinfunction "1_1") (pintype "passive"))
      (node (ref "C41") (pin "1") (pinfunction "1_1") (pintype "passive"))
      (node (ref "R29") (pin "2") (pinfunction "2_2") (pintype "passive"))
      (node (ref "R30") (pin "2") (pinfunction "2_2") (pintype "passive"))
      (node (ref "U$13") (pin "P$5") (pinfunction "VCC_P$5") (pintype "power_in"))
      (node (ref "U$14") (pin "P$5") (pinfunction "VCC_P$5") (pintype "power_in"))
      (node (ref "U$15") (pin "1") (pinfunction "OUT_1") (pintype "bidirectional"))
      (node (ref "U$17") (pin "5") (pinfunction "V+_5") (pintype "power_in"))
      (node (ref "U$18") (pin "5") (pinfunction "V+_5") (pintype "power_in"))
      (node (ref "U$7") (pin "5") (pinfunction "V+_5") (pintype "power_in"))
    )
    (net (code "62") (name "VDD") (class "Default")
      (node (ref "C13") (pin "1") (pinfunction "1_1") (pintype "passive"))
      (node (ref "C8") (pin "+") (pinfunction "+_+") (pintype "passive"))
      (node (ref "PWR1") (pin "1") (pinfunction "1_1") (pintype "passive"))
      (node (ref "Q2") (pin "5") (pinfunction "D_5") (pintype "passive"))
      (node (ref "Q2") (pin "6") (pinfunction "D1_6") (pintype "passive"))
      (node (ref "Q2") (pin "7") (pinfunction "D2_7") (pintype "passive"))
      (node (ref "Q2") (pin "8") (pinfunction "D3_8") (pintype "passive"))
      (node (ref "Q4") (pin "5") (pinfunction "D_5") (pintype "passive"))
      (node (ref "Q4") (pin "6") (pinfunction "D1_6") (pintype "passive"))
      (node (ref "Q4") (pin "7") (pinfunction "D2_7") (pintype "passive"))
      (node (ref "Q4") (pin "8") (pinfunction "D3_8") (pintype "passive"))
    )
    (net (code "63") (name "unconnected-(SWD1-Pad6)") (class "Default")
      (node (ref "SWD1") (pin "6") (pinfunction "6_6") (pintype "passive"))
    )
    (net (code "64") (name "unconnected-(U$12C-PA0-PadP$10)") (class "Default")
      (node (ref "U$12") (pin "P$10") (pinfunction "PA0_P$10") (pintype "bidirectional"))
    )
    (net (code "65") (name "unconnected-(U$12C-PA1-PadP$11)") (class "Default")
      (node (ref "U$12") (pin "P$11") (pinfunction "PA1_P$11") (pintype "bidirectional"))
    )
    (net (code "66") (name "unconnected-(U$12C-PA2-PadP$12)") (class "Default")
      (node (ref "U$12") (pin "P$12") (pinfunction "PA2_P$12") (pintype "bidirectional"))
    )
    (net (code "67") (name "unconnected-(U$12C-PA3-PadP$13)") (class "Default")
      (node (ref "U$12") (pin "P$13") (pinfunction "PA3_P$13") (pintype "bidirectional"))
    )
    (net (code "68") (name "unconnected-(U$12C-PA4-PadP$14)") (class "Default")
      (node (ref "U$12") (pin "P$14") (pinfunction "PA4_P$14") (pintype "bidirectional"))
    )
    (net (code "69") (name "unconnected-(U$12C-PA5-PadP$15)") (class "Default")
      (node (ref "U$12") (pin "P$15") (pinfunction "PA5_P$15") (pintype "bidirectional"))
    )
    (net (code "70") (name "unconnected-(U$12C-PA6-PadP$16)") (class "Default")
      (node (ref "U$12") (pin "P$16") (pinfunction "PA6_P$16") (pintype "bidirectional"))
    )
    (net (code "71") (name "unconnected-(U$12D-PA8-PadP$29)") (class "Default")
      (node (ref "U$12") (pin "P$29") (pinfunction "PA8_P$29") (pintype "bidirectional"))
    )
    (net (code "72") (name "unconnected-(U$12D-PA9-PadP$30)") (class "Default")
      (node (ref "U$12") (pin "P$30") (pinfunction "PA9_P$30") (pintype "bidirectional"))
    )
    (net (code "73") (name "unconnected-(U$12D-PA10-PadP$31)") (class "Default")
      (node (ref "U$12") (pin "P$31") (pinfunction "PA10_P$31") (pintype "bidirectional"))
    )
    (net (code "74") (name "unconnected-(U$12E-PB0-PadP$18)") (class "Default")
      (node (ref "U$12") (pin "P$18") (pinfunction "PB0_P$18") (pintype "bidirectional"))
    )
    (net (code "75") (name "unconnected-(U$12E-PB1-PadP$19)") (class "Default")
      (node (ref "U$12") (pin "P$19") (pinfunction "PB1_P$19") (pintype "bidirectional"))
    )
    (net (code "76") (name "unconnected-(U$12E-PB2-PadP$20)") (class "Default")
      (node (ref "U$12") (pin "P$20") (pinfunction "PB2_P$20") (pintype "bidirectional"))
    )
    (net (code "77") (name "unconnected-(U$12E-PB4-PadP$40)") (class "Default")
      (node (ref "U$12") (pin "P$40") (pinfunction "PB4_P$40") (pintype "bidirectional"))
    )
    (net (code "78") (name "unconnected-(U$12G-PC13-PadP$2)") (class "Default")
      (node (ref "U$12") (pin "P$2") (pinfunction "PC13_P$2") (pintype "bidirectional"))
    )
    (net (code "79") (name "unconnected-(U$12G-PD8-PadP$28)") (class "Default")
      (node (ref "U$12") (pin "P$28") (pinfunction "PD8_P$28") (pintype "bidirectional"))
    )
    (net (code "80") (name "unconnected-(U$12G-PE8-PadP$21)") (class "Default")
      (node (ref "U$12") (pin "P$21") (pinfunction "PE8_P$21") (pintype "bidirectional"))
    )
    (net (code "81") (name "unconnected-(U$12G-PE9-PadP$22)") (class "Default")
      (node (ref "U$12") (pin "P$22") (pinfunction "PE9_P$22") (pintype "bidirectional"))
    )
    (net (code "82") (name "unconnected-(U$12G-PF6-PadP$35)") (class "Default")
      (node (ref "U$12") (pin "P$35") (pinfunction "PF6_P$35") (pintype "bidirectional"))
    )
    (net (code "83") (name "unconnected-(U$12G-PF7-PadP$36)") (class "Default")
      (node (ref "U$12") (pin "P$36") (pinfunction "PF7_P$36") (pintype "bidirectional"))
    )
    (net (code "84") (name "unconnected-(U$16-ID-PadP$4)") (class "Default")
      (node (ref "U$16") (pin "P$4") (pinfunction "ID_P$4") (pintype "bidirectional"))
    )
    (net (code "85") (name "unconnected-(U$16-PadP$6)") (class "Default")
      (node (ref "U$16") (pin "P$6") (pinfunction "P$6_P$6") (pintype "no_connect"))
    )
    (net (code "86") (name "unconnected-(U$16-PadP$7)") (class "Default")
      (node (ref "U$16") (pin "P$7") (pinfunction "P$7_P$7") (pintype "no_connect"))
    )
    (net (code "87") (name "unconnected-(U$16-PadP$8)") (class "Default")
      (node (ref "U$16") (pin "P$8") (pinfunction "P$8_P$8") (pintype "no_connect"))
    )
    (net (code "88") (name "unconnected-(U$16-PadP$9)") (class "Default")
      (node (ref "U$16") (pin "P$9") (pinfunction "P$9_P$9") (pintype "no_connect"))
    )
  )
)
